# MCU.net
KiCad netlist of a schematic drawn in Altium Designer
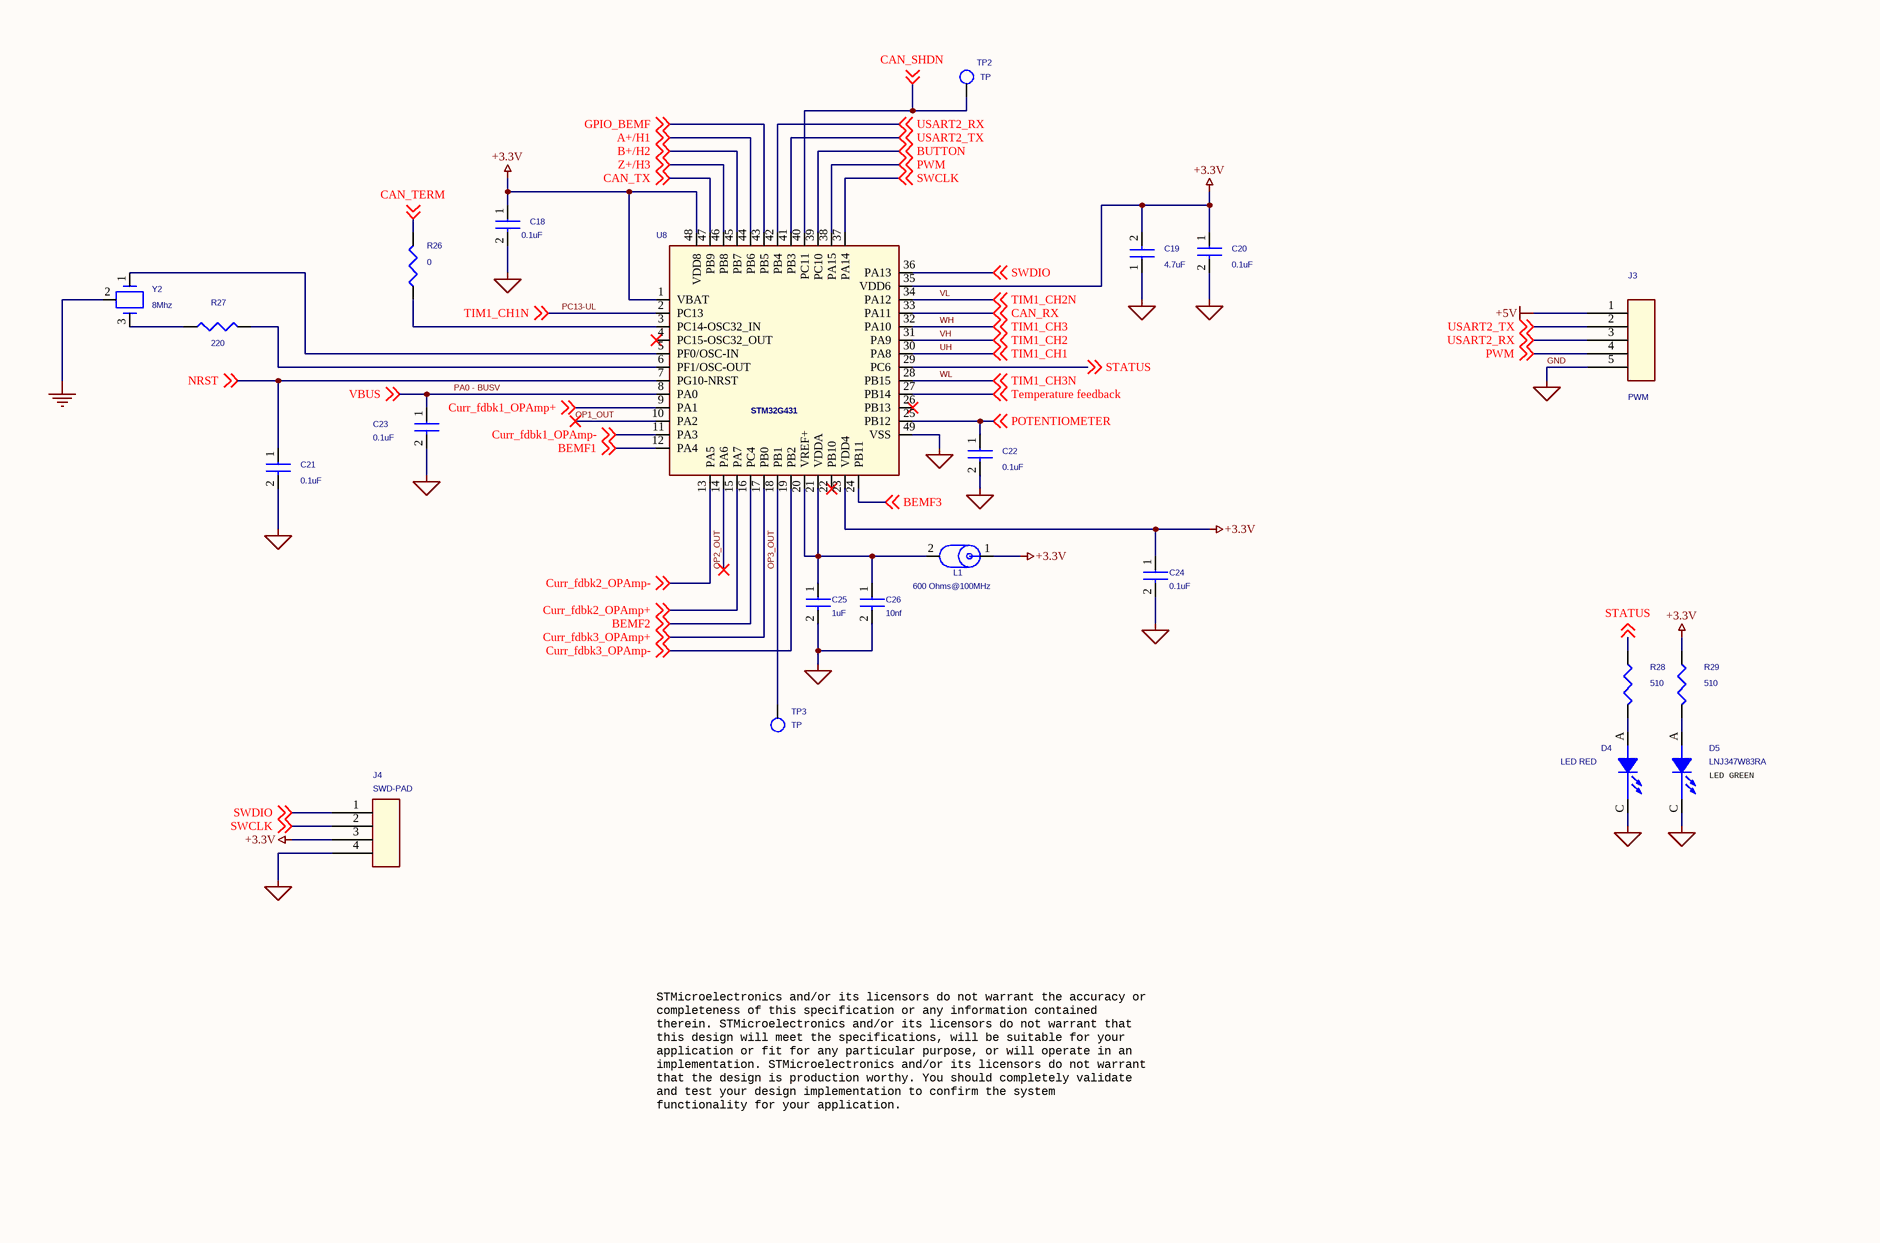
[diagram p0: MCU.SchDoc, top left]
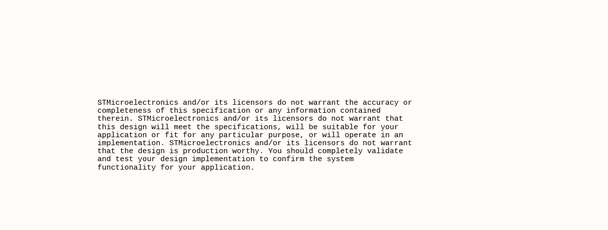
[diagram p1: MCU.SchDoc, bottom right]

(export (version "E")
  (design (tool "Eeschema 10.0.6"))
  (components
    (comp (ref "C18")
      (value "0.1uF")
      (footprint "C_0402")
      (description "CAP CER 0.1UF 16V X7R 0402")
      (fields (field (name "PART_NUMBER") "CAP-00000053") (field (name "TOLERANCE") "10%"))
      (libsource (lib "*") (part "CAP_Dup1"))
    )
    (comp (ref "C19")
      (value "4.7uF")
      (footprint "C_0603")
      (description "CAP CER 4.7UF 10V X5R 0603")
      (fields (field (name "MANUFACTURER") "Wurth Electronics Inc.") (field (name "TOLERANCE") "20%"))
      (libsource (lib "*") (part "CAP_Dup1"))
    )
    (comp (ref "C20")
      (value "0.1uF")
      (footprint "C_0402")
      (description "CAP CER 0.1UF 16V X7R 0402")
      (fields (field (name "MANUFACTURER") "Wurth Electronics Inc.") (field (name "TOLERANCE") "10%"))
      (libsource (lib "*") (part "CAP_Dup1"))
    )
    (comp (ref "C21")
      (value "0.1uF")
      (footprint "C_0402")
      (description "CAP CER 0.1UF 16V X7R 0402")
      (fields (field (name "MANUFACTURER") "Wurth Electronics Inc.") (field (name "TOLERANCE") "10%"))
      (libsource (lib "*") (part "CAP_Dup1"))
    )
    (comp (ref "C22")
      (value "0.1uF")
      (footprint "C_0402")
      (description "CAP CER 0.1UF 16V X7R 0402")
      (fields (field (name "PART_NUMBER") "CAP-00000053") (field (name "TOLERANCE") "10%"))
      (libsource (lib "*") (part "CAP_Dup1"))
    )
    (comp (ref "C23")
      (value "0.1uF")
      (footprint "C_0402")
      (description "CAP CER 0.1UF 16V X7R 0402")
      (fields (field (name "MANUFACTURER") "Wurth Electronics Inc.") (field (name "TOLERANCE") "10%"))
      (libsource (lib "*") (part "CAP_Dup1"))
    )
    (comp (ref "C24")
      (value "0.1uF")
      (footprint "C_0402")
      (description "CAP CER 0.1UF 16V X7R 0402")
      (fields (field (name "MANUFACTURER") "Wurth Electronics Inc.") (field (name "TOLERANCE") "10%"))
      (libsource (lib "*") (part "CAP_Dup1"))
    )
    (comp (ref "C25")
      (value "1uF")
      (footprint "C_0402")
      (description "CAP CER 1UF 25V X5R 0402")
      (fields (field (name "PART_NUMBER") "CAP-00000006") (field (name "TOLERANCE") "10%"))
      (libsource (lib "*") (part "CAP_Dup1"))
    )
    (comp (ref "C26")
      (value "10nf")
      (footprint "C_0402")
      (description "CAP CER 10000PF 16V X7R 0402")
      (fields (field (name "PART_NUMBER") "TMP-422") (field (name "TOLERANCE") "10%"))
      (libsource (lib "*") (part "CAP_Dup1"))
    )
    (comp (ref "D4")
      (value "LED RED")
      (footprint "D_0402_Led_red")
      (description "DIO, Rectangle with Flat Top, 1.00mm x 0.50mm, VLMS1500-GS08, 20mA, --, --, 0402 (1005 Metric)")
      (fields
        (field (name "PART_NUMBER") "DIO-00000003")
        (field (name "MANUFACTURER") "Vishay Semiconductor Opto Division")
      )
      (libsource (lib "*") (part "LED"))
    )
    (comp (ref "D5")
      (value "LNJ347W83RA")
      (footprint "D_0402_Led_green")
      (description "LED GREEN 0402 SMD")
      (fields (field (name "PART_NUMBER") "TMP-187") (field (name "MANUFACTURER") "Everlight Electronics"))
      (libsource (lib "*") (part "LED"))
    )
    (comp (ref "J3")
      (value "PWM")
      (footprint "SOLDER_PAD_5PIN_SMD")
      (description "SOLDER PADS")
      (libsource (lib "*") (part "CON5"))
    )
    (comp (ref "J4")
      (value "SWD-PAD")
      (footprint "SOLDER_PAD_4PIN_rect_SMD")
      (description "SOLDER PADS")
      (libsource (lib "*") (part "CON4"))
    )
    (comp (ref "L1")
      (value "600 Ohms@100MHz")
      (footprint "L_0402")
      (description "FERRITE BEAD 600 OHM 0402 1LN")
      (fields
        (field (name "MANUFACTURER") "Murata Electronics North America")
        (field (name "PART_NUMBER") "TMP-492")
      )
      (libsource (lib "*") (part "IND_FB"))
    )
    (comp (ref "R26")
      (value "0")
      (footprint "R_0402")
      (description "RES SMD 0 OHM JUMPER 1/16W 0402")
      (fields (field (name "PART_NUMBER") "RES-00000073") (field (name "TOLERANCE") "Jumper"))
      (libsource (lib "*") (part "RES"))
    )
    (comp (ref "R27")
      (value "220")
      (footprint "R_0402")
      (description "RES SMD 220 OHM 1% 1/16W 0402")
      (fields (field (name "PART_NUMBER") "TMP-437") (field (name "TOLERANCE") "1%"))
      (libsource (lib "*") (part "RES"))
    )
    (comp (ref "R28")
      (value "510")
      (footprint "R_0402")
      (description "RES SMD 510 OHM 1% 1/16W 0402")
      (fields (field (name "PART_NUMBER") "TMP-438") (field (name "TOLERANCE") "1%"))
      (libsource (lib "*") (part "RES"))
    )
    (comp (ref "R29")
      (value "510")
      (footprint "R_0402")
      (description "RES SMD 510 OHM 1% 1/16W 0402")
      (fields (field (name "PART_NUMBER") "TMP-438") (field (name "TOLERANCE") "1%"))
      (libsource (lib "*") (part "RES"))
    )
    (comp (ref "TP2")
      (value "TP")
      (footprint "test_point_100_smd")
      (description "TEST POINT 1MM  SMD PADSTASCK")
      (fields (field (name "PART_NUMBER") "TMP-386"))
      (libsource (lib "*") (part "TESTPOINT"))
    )
    (comp (ref "TP3")
      (value "TP")
      (footprint "test_point_100_smd")
      (description "TEST POINT 1MM  SMD PADSTASCK")
      (fields (field (name "PART_NUMBER") "TMP-386"))
      (libsource (lib "*") (part "TESTPOINT"))
    )
    (comp (ref "U8")
      (value "STM32G431")
      (footprint "qfn49p50_700x700x60l40x25t560n")
      (libsource (lib "*") (part "STM32_LQFP64_6"))
    )
    (comp (ref "Y2")
      (value "8Mhz")
      (footprint "murata_cstce8m00g15c99-r0")
      (description "CER RES 8.0000MHZ 33PF SMD")
      (fields
        (field (name "MANUFACTURER") "Murata Electronics North America")
        (field (name "PART_NUMBER") "TMP-382")
      )
      (libsource (lib "*") (part "resonator"))
    )
  )
  (nets
    (net (code "1") (name "+3.3V") (class "Default")
      (node (ref "C18") (pin "1") (pinfunction "1_1") (pintype "passive"))
      (node (ref "C19") (pin "2") (pinfunction "2_2") (pintype "passive"))
      (node (ref "C20") (pin "1") (pinfunction "1_1") (pintype "passive"))
      (node (ref "C24") (pin "1") (pinfunction "1_1") (pintype "passive"))
      (node (ref "J4") (pin "3") (pinfunction "3_3") (pintype "passive"))
      (node (ref "L1") (pin "1") (pinfunction "1_1") (pintype "passive"))
      (node (ref "R29") (pin "1") (pinfunction "1_1") (pintype "passive"))
      (node (ref "U8") (pin "1") (pinfunction "VBAT_1") (pintype "passive"))
      (node (ref "U8") (pin "23") (pinfunction "VDD4_23") (pintype "passive"))
      (node (ref "U8") (pin "35") (pinfunction "VDD6_35") (pintype "passive"))
      (node (ref "U8") (pin "48") (pinfunction "VDD8_48") (pintype "passive"))
    )
    (net (code "2") (name "+5V") (class "Default")
      (node (ref "J3") (pin "1") (pinfunction "1_1") (pintype "passive"))
    )
    (net (code "3") (name "/OP1_OUT") (class "Default")
      (node (ref "U8") (pin "10") (pinfunction "PA2_10") (pintype "passive+no_connect"))
    )
    (net (code "4") (name "/OP2_OUT") (class "Default")
      (node (ref "U8") (pin "14") (pinfunction "PA6_14") (pintype "passive+no_connect"))
    )
    (net (code "5") (name "/OP3_OUT") (class "Default")
      (node (ref "TP3") (pin "1") (pinfunction "1_1") (pintype "passive"))
      (node (ref "U8") (pin "18") (pinfunction "PB1_18") (pintype "passive"))
    )
    (net (code "6") (name "A+{slash}H1") (class "Default")
      (node (ref "U8") (pin "44") (pinfunction "PB6_44") (pintype "passive"))
    )
    (net (code "7") (name "B+{slash}H2") (class "Default")
      (node (ref "U8") (pin "45") (pinfunction "PB7_45") (pintype "passive"))
    )
    (net (code "8") (name "BEMF1") (class "Default")
      (node (ref "U8") (pin "12") (pinfunction "PA4_12") (pintype "passive"))
    )
    (net (code "9") (name "BEMF2") (class "Default")
      (node (ref "U8") (pin "16") (pinfunction "PC4_16") (pintype "passive"))
    )
    (net (code "10") (name "BEMF3") (class "Default")
      (node (ref "U8") (pin "24") (pinfunction "PB11_24") (pintype "passive"))
    )
    (net (code "11") (name "BUTTON") (class "Default")
      (node (ref "U8") (pin "39") (pinfunction "PC10_39") (pintype "passive"))
    )
    (net (code "12") (name "CAN_RX") (class "Default")
      (node (ref "U8") (pin "33") (pinfunction "PA11_33") (pintype "passive"))
    )
    (net (code "13") (name "CAN_SHDN") (class "Default")
      (node (ref "TP2") (pin "1") (pinfunction "1_1") (pintype "passive"))
      (node (ref "U8") (pin "40") (pinfunction "PC11_40") (pintype "passive"))
    )
    (net (code "14") (name "CAN_TERM") (class "Default")
      (node (ref "R26") (pin "2") (pinfunction "2_2") (pintype "passive"))
    )
    (net (code "15") (name "CAN_TX") (class "Default")
      (node (ref "U8") (pin "47") (pinfunction "PB9_47") (pintype "passive"))
    )
    (net (code "16") (name "Curr_fdbk1_OPAmp+") (class "Default")
      (node (ref "U8") (pin "9") (pinfunction "PA1_9") (pintype "passive"))
    )
    (net (code "17") (name "Curr_fdbk1_OPAmp-") (class "Default")
      (node (ref "U8") (pin "11") (pinfunction "PA3_11") (pintype "passive"))
    )
    (net (code "18") (name "Curr_fdbk2_OPAmp+") (class "Default")
      (node (ref "U8") (pin "15") (pinfunction "PA7_15") (pintype "passive"))
    )
    (net (code "19") (name "Curr_fdbk2_OPAmp-") (class "Default")
      (node (ref "U8") (pin "13") (pinfunction "PA5_13") (pintype "passive"))
    )
    (net (code "20") (name "Curr_fdbk3_OPAmp+") (class "Default")
      (node (ref "U8") (pin "17") (pinfunction "PB0_17") (pintype "passive"))
    )
    (net (code "21") (name "Curr_fdbk3_OPAmp-") (class "Default")
      (node (ref "U8") (pin "19") (pinfunction "PB2_19") (pintype "passive"))
    )
    (net (code "22") (name "GND") (class "Default")
      (node (ref "C18") (pin "2") (pinfunction "2_2") (pintype "passive"))
      (node (ref "C19") (pin "1") (pinfunction "1_1") (pintype "passive"))
      (node (ref "C20") (pin "2") (pinfunction "2_2") (pintype "passive"))
      (node (ref "C21") (pin "2") (pinfunction "2_2") (pintype "passive"))
      (node (ref "C22") (pin "2") (pinfunction "2_2") (pintype "passive"))
      (node (ref "C23") (pin "2") (pinfunction "2_2") (pintype "passive"))
      (node (ref "C24") (pin "2") (pinfunction "2_2") (pintype "passive"))
      (node (ref "C25") (pin "2") (pinfunction "2_2") (pintype "passive"))
      (node (ref "C26") (pin "2") (pinfunction "2_2") (pintype "passive"))
      (node (ref "D4") (pin "C") (pinfunction "CATHODE_C") (pintype "passive"))
      (node (ref "D5") (pin "C") (pinfunction "CATHODE_C") (pintype "passive"))
      (node (ref "J3") (pin "5") (pinfunction "5_5") (pintype "passive"))
      (node (ref "J4") (pin "4") (pinfunction "4_4") (pintype "passive"))
      (node (ref "U8") (pin "49") (pinfunction "VSS_49") (pintype "passive"))
      (node (ref "Y2") (pin "2") (pinfunction "2_2") (pintype "passive"))
    )
    (net (code "23") (name "GPIO_BEMF") (class "Default")
      (node (ref "U8") (pin "43") (pinfunction "PB5_43") (pintype "passive"))
    )
    (net (code "24") (name "NRST") (class "Default")
      (node (ref "C21") (pin "1") (pinfunction "1_1") (pintype "passive"))
      (node (ref "U8") (pin "7") (pinfunction "PG10-NRST_7") (pintype "passive"))
    )
    (net (code "25") (name "Net-(D4-ANODE)") (class "Default")
      (node (ref "D4") (pin "A") (pinfunction "ANODE_A") (pintype "passive"))
      (node (ref "R28") (pin "2") (pinfunction "2_2") (pintype "passive"))
    )
    (net (code "26") (name "Net-(D5-ANODE)") (class "Default")
      (node (ref "D5") (pin "A") (pinfunction "ANODE_A") (pintype "passive"))
      (node (ref "R29") (pin "2") (pinfunction "2_2") (pintype "passive"))
    )
    (net (code "27") (name "Net-(R27-Pad1)") (class "Default")
      (node (ref "R27") (pin "1") (pinfunction "1_1") (pintype "passive"))
      (node (ref "Y2") (pin "3") (pinfunction "3_3") (pintype "passive"))
    )
    (net (code "28") (name "Net-(U8-PC14-OSC32_IN)") (class "Default")
      (node (ref "R26") (pin "1") (pinfunction "1_1") (pintype "passive"))
      (node (ref "U8") (pin "3") (pinfunction "PC14-OSC32_IN_3") (pintype "passive"))
    )
    (net (code "29") (name "Net-(U8-PF0{slash}OSC-IN)") (class "Default")
      (node (ref "U8") (pin "5") (pinfunction "PF0/OSC-IN_5") (pintype "passive"))
      (node (ref "Y2") (pin "1") (pinfunction "1_1") (pintype "passive"))
    )
    (net (code "30") (name "Net-(U8-PF1{slash}OSC-OUT)") (class "Default")
      (node (ref "R27") (pin "2") (pinfunction "2_2") (pintype "passive"))
      (node (ref "U8") (pin "6") (pinfunction "PF1/OSC-OUT_6") (pintype "passive"))
    )
    (net (code "31") (name "Net-(U8-VDDA)") (class "Default")
      (node (ref "C25") (pin "1") (pinfunction "1_1") (pintype "passive"))
      (node (ref "C26") (pin "1") (pinfunction "1_1") (pintype "passive"))
      (node (ref "L1") (pin "2") (pinfunction "2_2") (pintype "passive"))
      (node (ref "U8") (pin "20") (pinfunction "VREF+_20") (pintype "passive"))
      (node (ref "U8") (pin "21") (pinfunction "VDDA_21") (pintype "passive"))
    )
    (net (code "32") (name "POTENTIOMETER") (class "Default")
      (node (ref "C22") (pin "1") (pinfunction "1_1") (pintype "passive"))
      (node (ref "U8") (pin "25") (pinfunction "PB12_25") (pintype "passive"))
    )
    (net (code "33") (name "PWM") (class "Default")
      (node (ref "J3") (pin "4") (pinfunction "4_4") (pintype "passive"))
      (node (ref "U8") (pin "38") (pinfunction "PA15_38") (pintype "passive"))
    )
    (net (code "34") (name "STATUS") (class "Default")
      (node (ref "R28") (pin "1") (pinfunction "1_1") (pintype "passive"))
      (node (ref "U8") (pin "29") (pinfunction "PC6_29") (pintype "passive"))
    )
    (net (code "35") (name "SWCLK") (class "Default")
      (node (ref "J4") (pin "2") (pinfunction "2_2") (pintype "passive"))
      (node (ref "U8") (pin "37") (pinfunction "PA14_37") (pintype "passive"))
    )
    (net (code "36") (name "SWDIO") (class "Default")
      (node (ref "J4") (pin "1") (pinfunction "1_1") (pintype "passive"))
      (node (ref "U8") (pin "36") (pinfunction "PA13_36") (pintype "passive"))
    )
    (net (code "37") (name "TIM1_CH1") (class "Default")
      (node (ref "U8") (pin "30") (pinfunction "PA8_30") (pintype "passive"))
    )
    (net (code "38") (name "TIM1_CH1N") (class "Default")
      (node (ref "U8") (pin "2") (pinfunction "PC13_2") (pintype "passive"))
    )
    (net (code "39") (name "TIM1_CH2") (class "Default")
      (node (ref "U8") (pin "31") (pinfunction "PA9_31") (pintype "passive"))
    )
    (net (code "40") (name "TIM1_CH2N") (class "Default")
      (node (ref "U8") (pin "34") (pinfunction "PA12_34") (pintype "passive"))
    )
    (net (code "41") (name "TIM1_CH3") (class "Default")
      (node (ref "U8") (pin "32") (pinfunction "PA10_32") (pintype "passive"))
    )
    (net (code "42") (name "TIM1_CH3N") (class "Default")
      (node (ref "U8") (pin "28") (pinfunction "PB15_28") (pintype "passive"))
    )
    (net (code "43") (name "Temperature feedback") (class "Default")
      (node (ref "U8") (pin "27") (pinfunction "PB14_27") (pintype "passive"))
    )
    (net (code "44") (name "USART2_RX") (class "Default")
      (node (ref "J3") (pin "3") (pinfunction "3_3") (pintype "passive"))
      (node (ref "U8") (pin "42") (pinfunction "PB4_42") (pintype "passive"))
    )
    (net (code "45") (name "USART2_TX") (class "Default")
      (node (ref "J3") (pin "2") (pinfunction "2_2") (pintype "passive"))
      (node (ref "U8") (pin "41") (pinfunction "PB3_41") (pintype "passive"))
    )
    (net (code "46") (name "VBUS") (class "Default")
      (node (ref "C23") (pin "1") (pinfunction "1_1") (pintype "passive"))
      (node (ref "U8") (pin "8") (pinfunction "PA0_8") (pintype "passive"))
    )
    (net (code "47") (name "Z+{slash}H3") (class "Default")
      (node (ref "U8") (pin "46") (pinfunction "PB8_46") (pintype "passive"))
    )
    (net (code "48") (name "unconnected-(U8-PB10-Pad22)") (class "Default")
      (node (ref "U8") (pin "22") (pinfunction "PB10_22") (pintype "passive+no_connect"))
    )
    (net (code "49") (name "unconnected-(U8-PB13-Pad26)") (class "Default")
      (node (ref "U8") (pin "26") (pinfunction "PB13_26") (pintype "passive+no_connect"))
    )
    (net (code "50") (name "unconnected-(U8-PC15-OSC32_OUT-Pad4)") (class "Default")
      (node (ref "U8") (pin "4") (pinfunction "PC15-OSC32_OUT_4") (pintype "passive+no_connect"))
    )
  )
)
